# scoreur.net
KiCad netlist of a schematic drawn in EAGLE
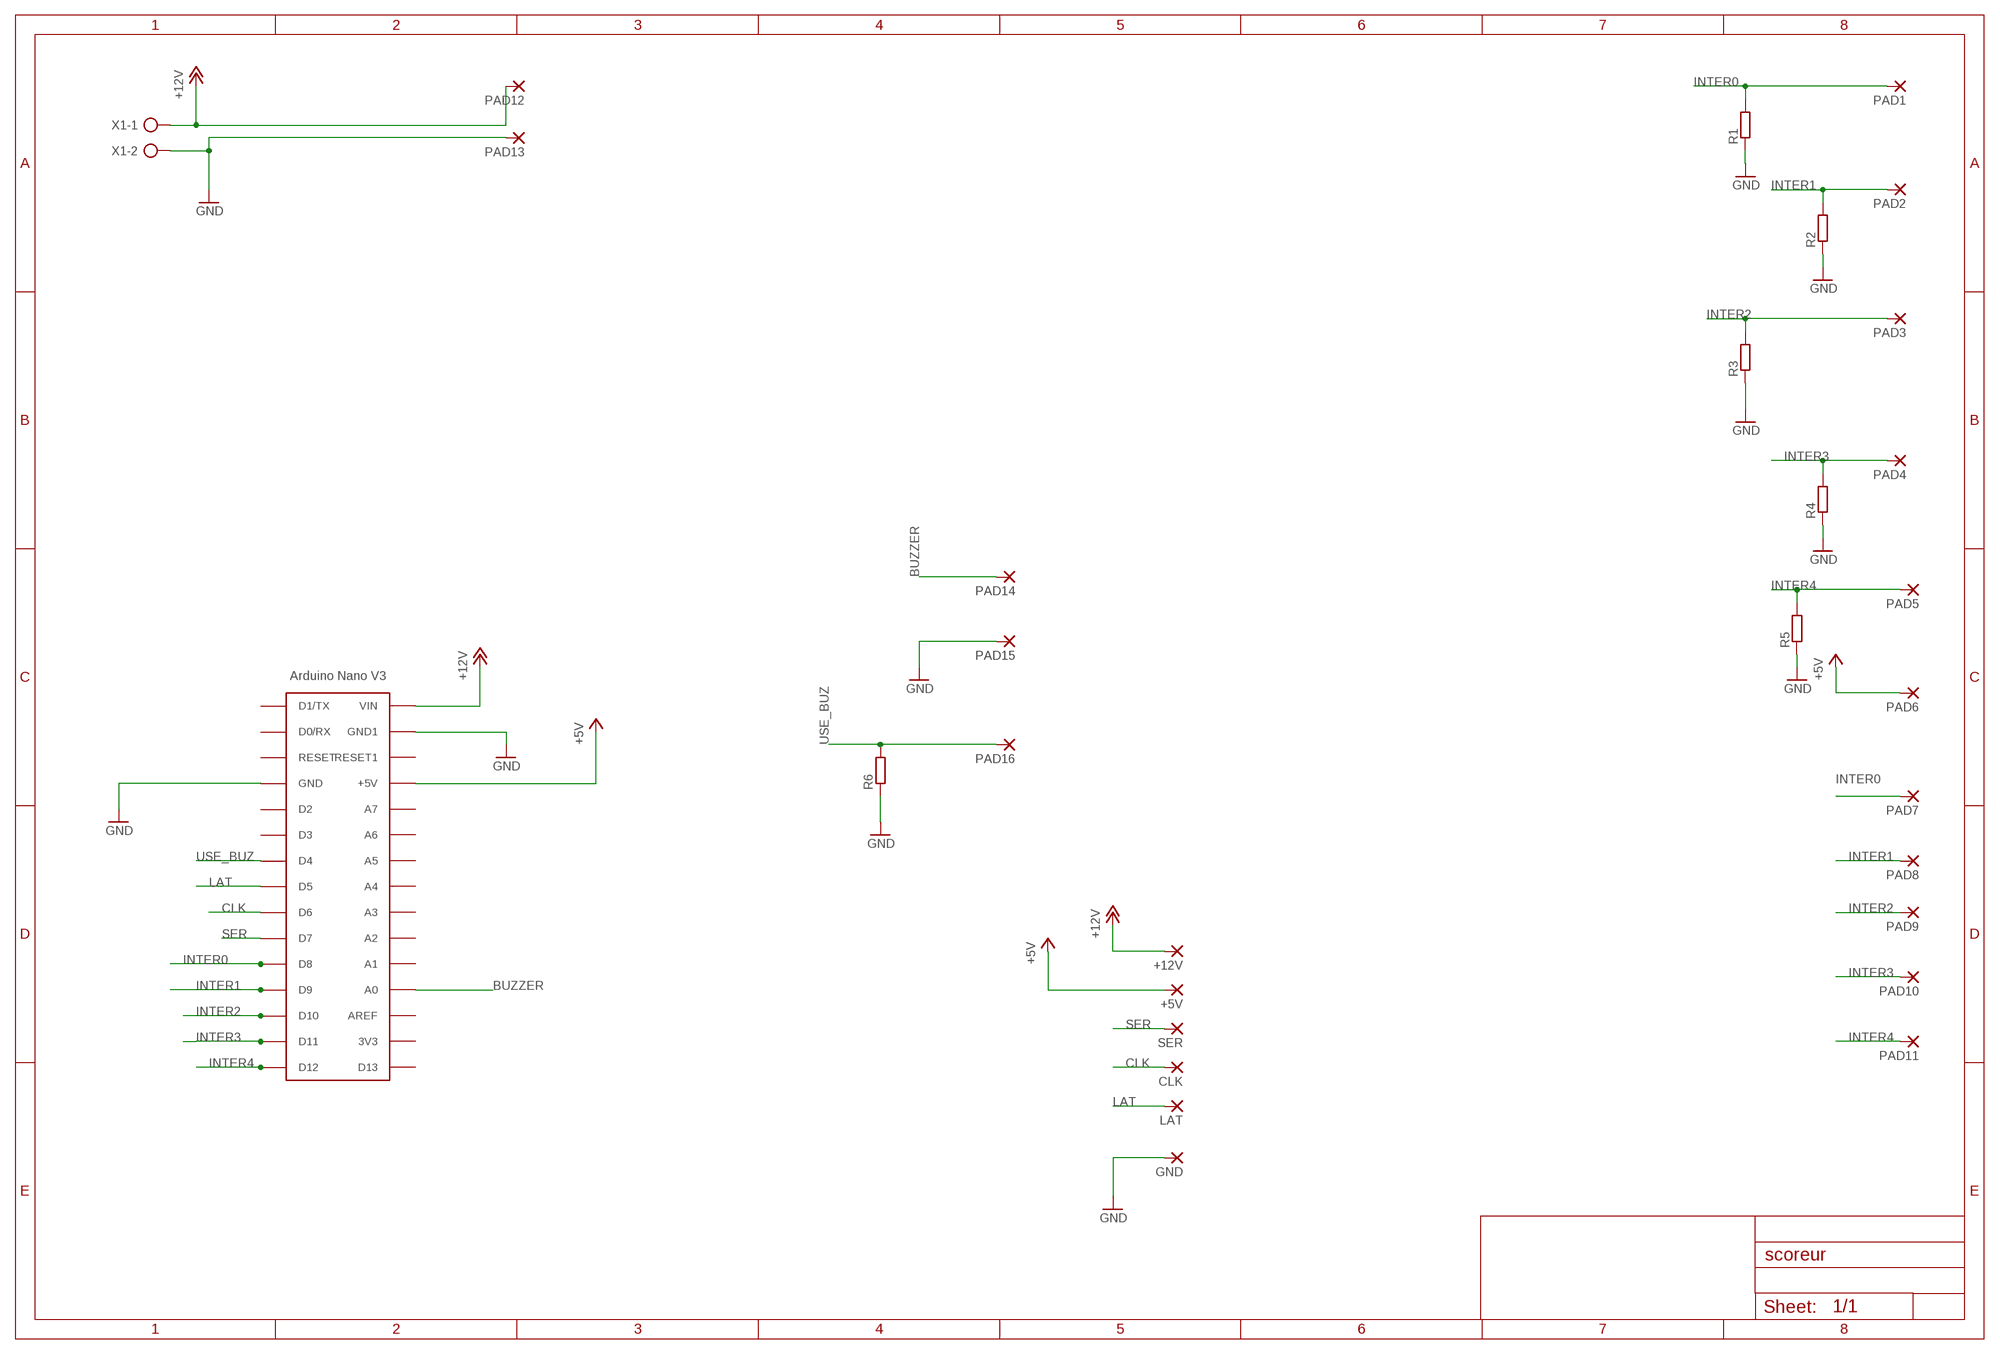
[diagram p0: schematic, sheet 1]

(export (version "E")
  (design (tool "Eeschema 10.0.6"))
  (components
    (comp (ref "+5V")
      (value "SMD5")
      (footprint "eagle-import:SMD2,54-5,08")
      (libsource (lib "eagle-import") (part "SMD5"))
    )
    (comp (ref "+12V")
      (value "SMD5")
      (footprint "eagle-import:SMD2,54-5,08")
      (libsource (lib "eagle-import") (part "SMD5"))
    )
    (comp (ref "CLK")
      (value "SMD5")
      (footprint "eagle-import:SMD2,54-5,08")
      (libsource (lib "eagle-import") (part "SMD5"))
    )
    (comp (ref "GND")
      (value "SMD5")
      (footprint "eagle-import:SMD2,54-5,08")
      (libsource (lib "eagle-import") (part "SMD5"))
    )
    (comp (ref "LAT")
      (value "SMD5")
      (footprint "eagle-import:SMD2,54-5,08")
      (libsource (lib "eagle-import") (part "SMD5"))
    )
    (comp (ref "PAD1")
      (value "SMD5")
      (footprint "eagle-import:SMD2,54-5,08")
      (libsource (lib "eagle-import") (part "SMD5"))
    )
    (comp (ref "PAD2")
      (value "SMD5")
      (footprint "eagle-import:SMD2,54-5,08")
      (libsource (lib "eagle-import") (part "SMD5"))
    )
    (comp (ref "PAD3")
      (value "SMD5")
      (footprint "eagle-import:SMD2,54-5,08")
      (libsource (lib "eagle-import") (part "SMD5"))
    )
    (comp (ref "PAD4")
      (value "SMD5")
      (footprint "eagle-import:SMD2,54-5,08")
      (libsource (lib "eagle-import") (part "SMD5"))
    )
    (comp (ref "PAD5")
      (value "SMD5")
      (footprint "eagle-import:SMD2,54-5,08")
      (libsource (lib "eagle-import") (part "SMD5"))
    )
    (comp (ref "PAD6")
      (value "SMD5")
      (footprint "eagle-import:SMD2,54-5,08")
      (libsource (lib "eagle-import") (part "SMD5"))
    )
    (comp (ref "PAD7")
      (value "SMD5")
      (footprint "eagle-import:SMD2,54-5,08")
      (libsource (lib "eagle-import") (part "SMD5"))
    )
    (comp (ref "PAD8")
      (value "SMD5")
      (footprint "eagle-import:SMD2,54-5,08")
      (libsource (lib "eagle-import") (part "SMD5"))
    )
    (comp (ref "PAD9")
      (value "SMD5")
      (footprint "eagle-import:SMD2,54-5,08")
      (libsource (lib "eagle-import") (part "SMD5"))
    )
    (comp (ref "PAD10")
      (value "SMD5")
      (footprint "eagle-import:SMD2,54-5,08")
      (libsource (lib "eagle-import") (part "SMD5"))
    )
    (comp (ref "PAD11")
      (value "SMD5")
      (footprint "eagle-import:SMD2,54-5,08")
      (libsource (lib "eagle-import") (part "SMD5"))
    )
    (comp (ref "PAD12")
      (value "SMD5")
      (footprint "eagle-import:SMD2,54-5,08")
      (libsource (lib "eagle-import") (part "SMD5"))
    )
    (comp (ref "PAD13")
      (value "SMD5")
      (footprint "eagle-import:SMD2,54-5,08")
      (libsource (lib "eagle-import") (part "SMD5"))
    )
    (comp (ref "PAD14")
      (value "SMD5")
      (footprint "eagle-import:SMD2,54-5,08")
      (libsource (lib "eagle-import") (part "SMD5"))
    )
    (comp (ref "PAD15")
      (value "SMD5")
      (footprint "eagle-import:SMD2,54-5,08")
      (libsource (lib "eagle-import") (part "SMD5"))
    )
    (comp (ref "PAD16")
      (value "SMD5")
      (footprint "eagle-import:SMD2,54-5,08")
      (libsource (lib "eagle-import") (part "SMD5"))
    )
    (comp (ref "R1")
      (value "R-EU_R1206")
      (footprint "eagle-import:R1206")
      (libsource (lib "eagle-import") (part "R-EU_R1206"))
    )
    (comp (ref "R2")
      (value "R-EU_R1206")
      (footprint "eagle-import:R1206")
      (libsource (lib "eagle-import") (part "R-EU_R1206"))
    )
    (comp (ref "R3")
      (value "R-EU_R1206")
      (footprint "eagle-import:R1206")
      (libsource (lib "eagle-import") (part "R-EU_R1206"))
    )
    (comp (ref "R4")
      (value "R-EU_R1206")
      (footprint "eagle-import:R1206")
      (libsource (lib "eagle-import") (part "R-EU_R1206"))
    )
    (comp (ref "R5")
      (value "R-EU_R1206")
      (footprint "eagle-import:R1206")
      (libsource (lib "eagle-import") (part "R-EU_R1206"))
    )
    (comp (ref "R6")
      (value "R-EU_R1206")
      (footprint "eagle-import:R1206")
      (libsource (lib "eagle-import") (part "R-EU_R1206"))
    )
    (comp (ref "SER")
      (value "SMD5")
      (footprint "eagle-import:SMD2,54-5,08")
      (libsource (lib "eagle-import") (part "SMD5"))
    )
    (comp (ref "U$1")
      (value "ARDUINONANO")
      (footprint "eagle-import:PDIP-32")
      (libsource (lib "eagle-import") (part "ARDUINONANO"))
    )
    (comp (ref "X1")
      (value "AK500/2-H")
      (footprint "eagle-import:AK500_2-H")
      (libsource (lib "eagle-import") (part "AK500/2-H"))
    )
  )
  (nets
    (net (code "1") (name "+5V") (class "Default")
      (node (ref "+5V") (pin "1") (pinfunction "P_1") (pintype "passive"))
      (node (ref "PAD6") (pin "1") (pinfunction "P_1") (pintype "passive"))
      (node (ref "U$1") (pin "+5V") (pinfunction "+5V_+5V") (pintype "bidirectional"))
    )
    (net (code "2") (name "+12V") (class "Default")
      (node (ref "+12V") (pin "1") (pinfunction "P_1") (pintype "passive"))
      (node (ref "PAD12") (pin "1") (pinfunction "P_1") (pintype "passive"))
      (node (ref "U$1") (pin "VIN") (pinfunction "VIN_VIN") (pintype "bidirectional"))
      (node (ref "X1") (pin "1") (pinfunction "KL_1") (pintype "passive"))
    )
    (net (code "3") (name "/BUZZER") (class "Default")
      (node (ref "PAD14") (pin "1") (pinfunction "P_1") (pintype "passive"))
      (node (ref "U$1") (pin "A7") (pinfunction "A0_A7") (pintype "bidirectional"))
    )
    (net (code "4") (name "/CLK") (class "Default")
      (node (ref "CLK") (pin "1") (pinfunction "P_1") (pintype "passive"))
      (node (ref "U$1") (pin "D6") (pinfunction "D6_D6") (pintype "bidirectional"))
    )
    (net (code "5") (name "/INTER0") (class "Default")
      (node (ref "PAD1") (pin "1") (pinfunction "P_1") (pintype "passive"))
      (node (ref "PAD7") (pin "1") (pinfunction "P_1") (pintype "passive"))
      (node (ref "R1") (pin "2") (pinfunction "2_2") (pintype "passive"))
      (node (ref "U$1") (pin "D8") (pinfunction "D8_D8") (pintype "bidirectional"))
    )
    (net (code "6") (name "/INTER1") (class "Default")
      (node (ref "PAD2") (pin "1") (pinfunction "P_1") (pintype "passive"))
      (node (ref "PAD8") (pin "1") (pinfunction "P_1") (pintype "passive"))
      (node (ref "R2") (pin "2") (pinfunction "2_2") (pintype "passive"))
      (node (ref "U$1") (pin "D9") (pinfunction "D9_D9") (pintype "bidirectional"))
    )
    (net (code "7") (name "/INTER2") (class "Default")
      (node (ref "PAD3") (pin "1") (pinfunction "P_1") (pintype "passive"))
      (node (ref "PAD9") (pin "1") (pinfunction "P_1") (pintype "passive"))
      (node (ref "R3") (pin "2") (pinfunction "2_2") (pintype "passive"))
      (node (ref "U$1") (pin "D10") (pinfunction "D10_D10") (pintype "bidirectional"))
    )
    (net (code "8") (name "/INTER3") (class "Default")
      (node (ref "PAD10") (pin "1") (pinfunction "P_1") (pintype "passive"))
      (node (ref "PAD4") (pin "1") (pinfunction "P_1") (pintype "passive"))
      (node (ref "R4") (pin "2") (pinfunction "2_2") (pintype "passive"))
      (node (ref "U$1") (pin "D11") (pinfunction "D11_D11") (pintype "bidirectional"))
    )
    (net (code "9") (name "/INTER4") (class "Default")
      (node (ref "PAD11") (pin "1") (pinfunction "P_1") (pintype "passive"))
      (node (ref "PAD5") (pin "1") (pinfunction "P_1") (pintype "passive"))
      (node (ref "R5") (pin "2") (pinfunction "2_2") (pintype "passive"))
      (node (ref "U$1") (pin "D12") (pinfunction "D12_D12") (pintype "bidirectional"))
    )
    (net (code "10") (name "/LAT") (class "Default")
      (node (ref "LAT") (pin "1") (pinfunction "P_1") (pintype "passive"))
      (node (ref "U$1") (pin "D5") (pinfunction "D5_D5") (pintype "bidirectional"))
    )
    (net (code "11") (name "/SER") (class "Default")
      (node (ref "SER") (pin "1") (pinfunction "P_1") (pintype "passive"))
      (node (ref "U$1") (pin "D7") (pinfunction "D7_D7") (pintype "bidirectional"))
    )
    (net (code "12") (name "/USE_BUZ") (class "Default")
      (node (ref "PAD16") (pin "1") (pinfunction "P_1") (pintype "passive"))
      (node (ref "R6") (pin "2") (pinfunction "2_2") (pintype "passive"))
      (node (ref "U$1") (pin "D4") (pinfunction "D4_D4") (pintype "bidirectional"))
    )
    (net (code "13") (name "GND") (class "Default")
      (node (ref "GND") (pin "1") (pinfunction "P_1") (pintype "passive"))
      (node (ref "PAD13") (pin "1") (pinfunction "P_1") (pintype "passive"))
      (node (ref "PAD15") (pin "1") (pinfunction "P_1") (pintype "passive"))
      (node (ref "R1") (pin "1") (pinfunction "1_1") (pintype "passive"))
      (node (ref "R2") (pin "1") (pinfunction "1_1") (pintype "passive"))
      (node (ref "R3") (pin "1") (pinfunction "1_1") (pintype "passive"))
      (node (ref "R4") (pin "1") (pinfunction "1_1") (pintype "passive"))
      (node (ref "R5") (pin "1") (pinfunction "1_1") (pintype "passive"))
      (node (ref "R6") (pin "1") (pinfunction "1_1") (pintype "passive"))
      (node (ref "U$1") (pin "GND") (pinfunction "GND_GND") (pintype "bidirectional"))
      (node (ref "U$1") (pin "GND1") (pinfunction "GND1_GND1") (pintype "bidirectional"))
      (node (ref "X1") (pin "2") (pinfunction "KL_2") (pintype "passive"))
    )
    (net (code "14") (name "unconnected-(U$1-A1-PadA6)") (class "Default")
      (node (ref "U$1") (pin "A6") (pinfunction "A1_A6") (pintype "bidirectional"))
    )
    (net (code "15") (name "unconnected-(U$1-A2-PadA5)") (class "Default")
      (node (ref "U$1") (pin "A5") (pinfunction "A2_A5") (pintype "bidirectional"))
    )
    (net (code "16") (name "unconnected-(U$1-A3-PadA4)") (class "Default")
      (node (ref "U$1") (pin "A4") (pinfunction "A3_A4") (pintype "bidirectional"))
    )
    (net (code "17") (name "unconnected-(U$1-A4-PadA3)") (class "Default")
      (node (ref "U$1") (pin "A3") (pinfunction "A4_A3") (pintype "bidirectional"))
    )
    (net (code "18") (name "unconnected-(U$1-A5-PadA2)") (class "Default")
      (node (ref "U$1") (pin "A2") (pinfunction "A5_A2") (pintype "bidirectional"))
    )
    (net (code "19") (name "unconnected-(U$1-A6-PadA1)") (class "Default")
      (node (ref "U$1") (pin "A1") (pinfunction "A6_A1") (pintype "bidirectional"))
    )
    (net (code "20") (name "unconnected-(U$1-A7-PadA0)") (class "Default")
      (node (ref "U$1") (pin "A0") (pinfunction "A7_A0") (pintype "bidirectional"))
    )
    (net (code "21") (name "unconnected-(U$1-Pad3V3)") (class "Default")
      (node (ref "U$1") (pin "3V3") (pinfunction "3V3_3V3") (pintype "bidirectional"))
    )
    (net (code "22") (name "unconnected-(U$1-PadAREF)") (class "Default")
      (node (ref "U$1") (pin "AREF") (pinfunction "AREF_AREF") (pintype "bidirectional"))
    )
    (net (code "23") (name "unconnected-(U$1-PadD0{slash}RX)") (class "Default")
      (node (ref "U$1") (pin "D0/RX") (pinfunction "D0/RX_D0/RX") (pintype "bidirectional"))
    )
    (net (code "24") (name "unconnected-(U$1-PadD1{slash}TX)") (class "Default")
      (node (ref "U$1") (pin "D1/TX") (pinfunction "D1/TX_D1/TX") (pintype "bidirectional"))
    )
    (net (code "25") (name "unconnected-(U$1-PadD2)") (class "Default")
      (node (ref "U$1") (pin "D2") (pinfunction "D2_D2") (pintype "bidirectional"))
    )
    (net (code "26") (name "unconnected-(U$1-PadD3)") (class "Default")
      (node (ref "U$1") (pin "D3") (pinfunction "D3_D3") (pintype "bidirectional"))
    )
    (net (code "27") (name "unconnected-(U$1-PadD13)") (class "Default")
      (node (ref "U$1") (pin "D13") (pinfunction "D13_D13") (pintype "bidirectional"))
    )
    (net (code "28") (name "unconnected-(U$1-PadRESET)") (class "Default")
      (node (ref "U$1") (pin "RESET") (pinfunction "RESET_RESET") (pintype "bidirectional"))
    )
    (net (code "29") (name "unconnected-(U$1-PadRESET1)") (class "Default")
      (node (ref "U$1") (pin "RESET1") (pinfunction "RESET1_RESET1") (pintype "bidirectional"))
    )
  )
)
